# Connectors.net
KiCad netlist of a schematic drawn in Altium Designer
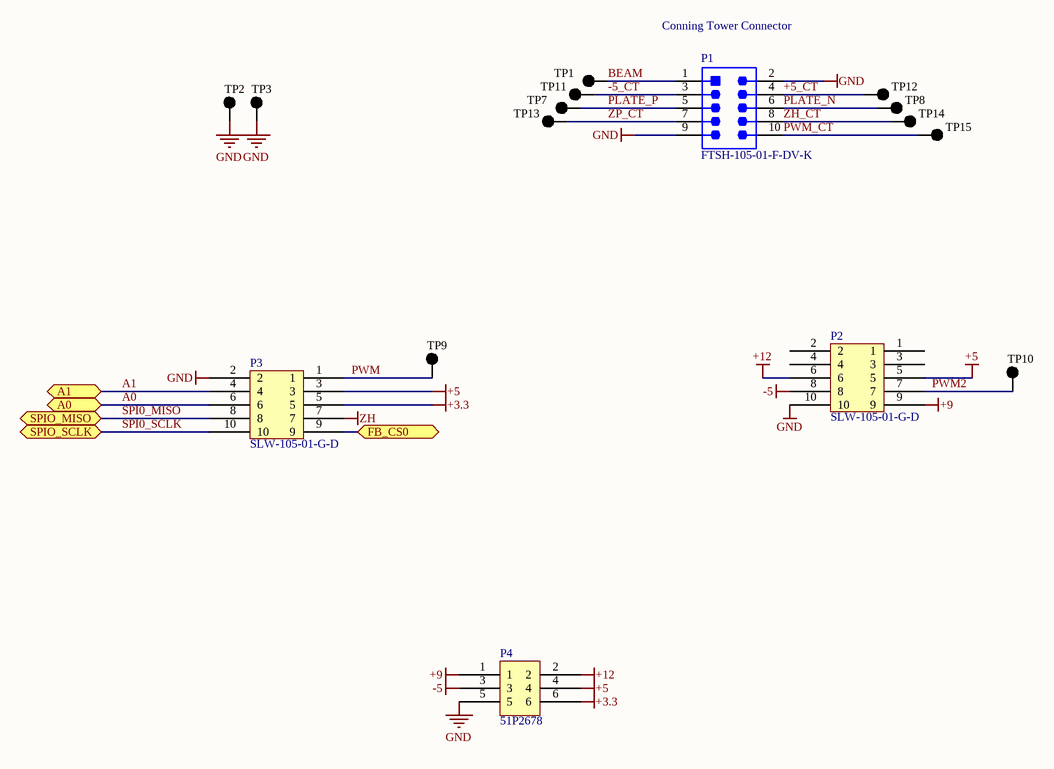
[diagram p0: Connectors.SchDoc]

(export (version "E")
  (design (tool "Eeschema 10.0.6"))
  (components
    (comp (ref "P1")
      (value "FTSH-105-01-F-DV-K")
      (footprint "SMTC-FTSH-105-01-L-DV-K_V")
      (description "Male Header, Pitch 1.27 mm, 2 x 5 Position, Height 6.12 mm, RoHS, Tube")
      (fields (field (name "MANUFACTURER") "Samtec"))
      (libsource (lib "Altium Content Vault") (part "CN-2P-M-R10"))
    )
    (comp (ref "P2")
      (value "SLW-105-01-G-D")
      (footprint "SLW-105-01-G-D")
      (description "CONN RCPT .100\" 10POS DUAL GOLD")
      (fields (field (name "MANUFACTURER") "Samtec Inc."))
      (libsource (lib "ZLS_Schematic_lib") (part "SLW-105-01-G-D"))
    )
    (comp (ref "P3")
      (value "SLW-105-01-G-D")
      (footprint "SLW-105-01-G-D")
      (description "CONN RCPT .100\" 10POS DUAL GOLD")
      (fields (field (name "MANUFACTURER") "Samtec Inc."))
      (libsource (lib "ZLS_Schematic_lib") (part "SLW-105-01-G-D"))
    )
    (comp (ref "P4")
      (value "IPL1-103-01-F-D")
      (footprint "IPL1-103-01-F-D")
      (fields (field (name "SUPPLIER PART NUMBER 1") "51P2678"))
      (libsource (lib "ZLS_Schematic_lib") (part "IPL1-103-01-F-D"))
    )
    (comp (ref "TP1")
      (value "5011")
      (footprint "KSTN-5011_V")
      (description "Test Point, Black, Through Hole, RoHS, Bulk")
      (fields (field (name "MANUFACTURER") "Keystone"))
      (libsource (lib "Altium Content Vault") (part "CMP-1672-00003-4"))
    )
    (comp (ref "TP2")
      (value "5011")
      (footprint "KSTN-5011_V")
      (description "Test Point, Black, Through Hole, RoHS, Bulk")
      (fields (field (name "MANUFACTURER") "Keystone"))
      (libsource (lib "Altium Content Vault") (part "CMP-1672-00003-4"))
    )
    (comp (ref "TP3")
      (value "5011")
      (footprint "KSTN-5011_V")
      (description "Test Point, Black, Through Hole, RoHS, Bulk")
      (fields (field (name "MANUFACTURER") "Keystone"))
      (libsource (lib "Altium Content Vault") (part "CMP-1672-00003-4"))
    )
    (comp (ref "TP7")
      (value "5011")
      (footprint "KSTN-5011_V")
      (description "Test Point, Black, Through Hole, RoHS, Bulk")
      (fields (field (name "MANUFACTURER") "Keystone"))
      (libsource (lib "Altium Content Vault") (part "CMP-1672-00003-4"))
    )
    (comp (ref "TP8")
      (value "5011")
      (footprint "KSTN-5011_V")
      (description "Test Point, Black, Through Hole, RoHS, Bulk")
      (fields (field (name "MANUFACTURER") "Keystone"))
      (libsource (lib "Altium Content Vault") (part "CMP-1672-00003-4"))
    )
    (comp (ref "TP9")
      (value "5011")
      (footprint "KSTN-5011_V")
      (description "Test Point, Black, Through Hole, RoHS, Bulk")
      (fields (field (name "MANUFACTURER") "Keystone"))
      (libsource (lib "Altium Content Vault") (part "CMP-1672-00003-4"))
    )
    (comp (ref "TP10")
      (value "5011")
      (footprint "KSTN-5011_V")
      (description "Test Point, Black, Through Hole, RoHS, Bulk")
      (fields (field (name "MANUFACTURER") "Keystone"))
      (libsource (lib "Altium Content Vault") (part "CMP-1672-00003-4"))
    )
    (comp (ref "TP11")
      (value "5011")
      (footprint "KSTN-5011_V")
      (description "Test Point, Black, Through Hole, RoHS, Bulk")
      (fields (field (name "MANUFACTURER") "Keystone"))
      (libsource (lib "Altium Content Vault") (part "CMP-1672-00003-4"))
    )
    (comp (ref "TP12")
      (value "5011")
      (footprint "KSTN-5011_V")
      (description "Test Point, Black, Through Hole, RoHS, Bulk")
      (fields (field (name "MANUFACTURER") "Keystone"))
      (libsource (lib "Altium Content Vault") (part "CMP-1672-00003-4"))
    )
    (comp (ref "TP13")
      (value "5011")
      (footprint "KSTN-5011_V")
      (description "Test Point, Black, Through Hole, RoHS, Bulk")
      (fields (field (name "MANUFACTURER") "Keystone"))
      (libsource (lib "Altium Content Vault") (part "CMP-1672-00003-4"))
    )
    (comp (ref "TP14")
      (value "5011")
      (footprint "KSTN-5011_V")
      (description "Test Point, Black, Through Hole, RoHS, Bulk")
      (fields (field (name "MANUFACTURER") "Keystone"))
      (libsource (lib "Altium Content Vault") (part "CMP-1672-00003-4"))
    )
    (comp (ref "TP15")
      (value "5011")
      (footprint "KSTN-5011_V")
      (description "Test Point, Black, Through Hole, RoHS, Bulk")
      (fields (field (name "MANUFACTURER") "Keystone"))
      (libsource (lib "Altium Content Vault") (part "CMP-1672-00003-4"))
    )
  )
  (nets
    (net (code "1") (name "+3.3") (class "Default")
      (node (ref "P3") (pin "5") (pinfunction "5_5") (pintype "passive"))
      (node (ref "P4") (pin "6") (pinfunction "6_6") (pintype "passive"))
    )
    (net (code "2") (name "+5") (class "Default")
      (node (ref "P2") (pin "5") (pinfunction "5_5") (pintype "passive"))
      (node (ref "P3") (pin "3") (pinfunction "3_3") (pintype "passive"))
      (node (ref "P4") (pin "4") (pinfunction "4_4") (pintype "passive"))
    )
    (net (code "3") (name "+9") (class "Default")
      (node (ref "P2") (pin "9") (pinfunction "9_9") (pintype "passive"))
      (node (ref "P4") (pin "1") (pinfunction "1_1") (pintype "passive"))
    )
    (net (code "4") (name "+12") (class "Default")
      (node (ref "P2") (pin "6") (pinfunction "6_6") (pintype "passive"))
      (node (ref "P4") (pin "2") (pinfunction "2_2") (pintype "passive"))
    )
    (net (code "5") (name "-5") (class "Default")
      (node (ref "P2") (pin "8") (pinfunction "8_8") (pintype "passive"))
      (node (ref "P4") (pin "3") (pinfunction "3_3") (pintype "passive"))
    )
    (net (code "6") (name "/+5_CT") (class "Default")
      (node (ref "P1") (pin "4") (pinfunction "4_4") (pintype "passive"))
      (node (ref "TP12") (pin "1") (pinfunction "1_1") (pintype "passive"))
    )
    (net (code "7") (name "/-5_CT") (class "Default")
      (node (ref "P1") (pin "3") (pinfunction "3_3") (pintype "passive"))
      (node (ref "TP11") (pin "1") (pinfunction "1_1") (pintype "passive"))
    )
    (net (code "8") (name "/A0") (class "Default")
      (node (ref "P3") (pin "6") (pinfunction "6_6") (pintype "passive"))
    )
    (net (code "9") (name "/A1") (class "Default")
      (node (ref "P3") (pin "4") (pinfunction "4_4") (pintype "passive"))
    )
    (net (code "10") (name "/BEAM") (class "Default")
      (node (ref "P1") (pin "1") (pinfunction "1_1") (pintype "passive"))
      (node (ref "TP1") (pin "1") (pinfunction "1_1") (pintype "passive"))
    )
    (net (code "11") (name "/FB_CS0") (class "Default")
      (node (ref "P3") (pin "9") (pinfunction "9_9") (pintype "passive"))
    )
    (net (code "12") (name "/PLATE_N") (class "Default")
      (node (ref "P1") (pin "6") (pinfunction "6_6") (pintype "passive"))
      (node (ref "TP8") (pin "1") (pinfunction "1_1") (pintype "passive"))
    )
    (net (code "13") (name "/PLATE_P") (class "Default")
      (node (ref "P1") (pin "5") (pinfunction "5_5") (pintype "passive"))
      (node (ref "TP7") (pin "1") (pinfunction "1_1") (pintype "passive"))
    )
    (net (code "14") (name "/PWM") (class "Default")
      (node (ref "P3") (pin "1") (pinfunction "1_1") (pintype "passive"))
      (node (ref "TP9") (pin "1") (pinfunction "1_1") (pintype "passive"))
    )
    (net (code "15") (name "/PWM2") (class "Default")
      (node (ref "P2") (pin "7") (pinfunction "7_7") (pintype "passive"))
      (node (ref "TP10") (pin "1") (pinfunction "1_1") (pintype "passive"))
    )
    (net (code "16") (name "/PWM_CT") (class "Default")
      (node (ref "P1") (pin "10") (pinfunction "10_10") (pintype "passive"))
      (node (ref "TP15") (pin "1") (pinfunction "1_1") (pintype "passive"))
    )
    (net (code "17") (name "/SPI0_MISO") (class "Default")
      (node (ref "P3") (pin "8") (pinfunction "8_8") (pintype "passive"))
    )
    (net (code "18") (name "/SPI0_SCLK") (class "Default")
      (node (ref "P3") (pin "10") (pinfunction "10_10") (pintype "passive"))
    )
    (net (code "19") (name "/ZH_CT") (class "Default")
      (node (ref "P1") (pin "8") (pinfunction "8_8") (pintype "passive"))
      (node (ref "TP14") (pin "1") (pinfunction "1_1") (pintype "passive"))
    )
    (net (code "20") (name "/ZP_CT") (class "Default")
      (node (ref "P1") (pin "7") (pinfunction "7_7") (pintype "passive"))
      (node (ref "TP13") (pin "1") (pinfunction "1_1") (pintype "passive"))
    )
    (net (code "21") (name "GND") (class "Default")
      (node (ref "P1") (pin "2") (pinfunction "2_2") (pintype "passive"))
      (node (ref "P1") (pin "9") (pinfunction "9_9") (pintype "passive"))
      (node (ref "P2") (pin "10") (pinfunction "10_10") (pintype "passive"))
      (node (ref "P3") (pin "2") (pinfunction "2_2") (pintype "passive"))
      (node (ref "P4") (pin "5") (pinfunction "5_5") (pintype "passive"))
      (node (ref "TP2") (pin "1") (pinfunction "1_1") (pintype "passive"))
      (node (ref "TP3") (pin "1") (pinfunction "1_1") (pintype "passive"))
    )
    (net (code "22") (name "ZH") (class "Default")
      (node (ref "P3") (pin "7") (pinfunction "7_7") (pintype "passive"))
    )
    (net (code "23") (name "unconnected-(P2-Pad1)") (class "Default")
      (node (ref "P2") (pin "1") (pinfunction "1_1") (pintype "passive"))
    )
    (net (code "24") (name "unconnected-(P2-Pad2)") (class "Default")
      (node (ref "P2") (pin "2") (pinfunction "2_2") (pintype "passive"))
    )
    (net (code "25") (name "unconnected-(P2-Pad3)") (class "Default")
      (node (ref "P2") (pin "3") (pinfunction "3_3") (pintype "passive"))
    )
    (net (code "26") (name "unconnected-(P2-Pad4)") (class "Default")
      (node (ref "P2") (pin "4") (pinfunction "4_4") (pintype "passive"))
    )
  )
)
